# ASL2112.net
KiCad netlist of a schematic drawn in EAGLE
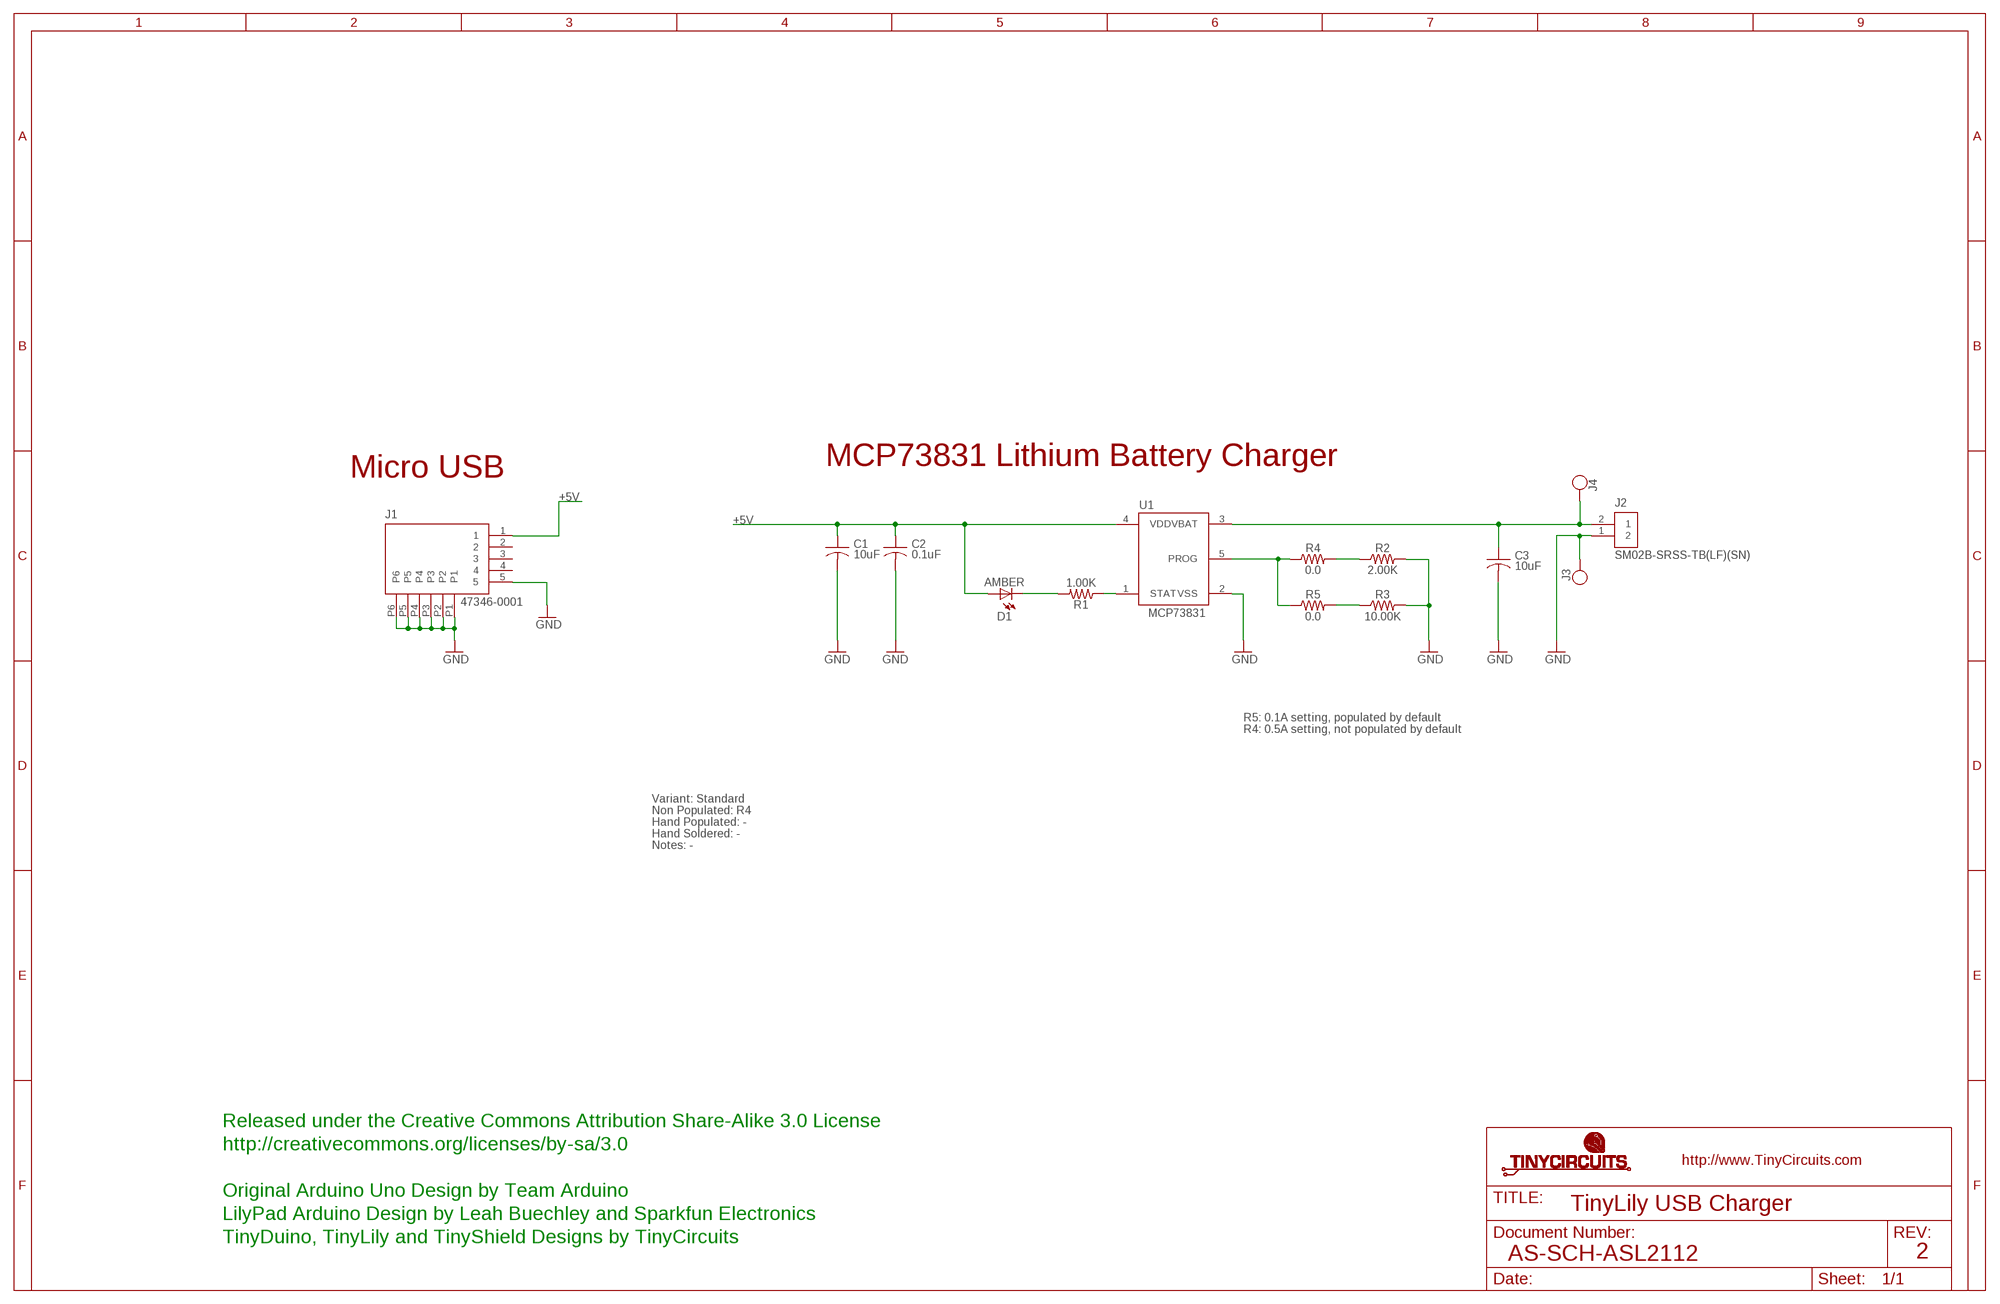
[diagram p0: schematic, sheet 1]

(export (version "E")
  (design (tool "Eeschema 10.0.6"))
  (components
    (comp (ref "C1")
      (value "10uF")
      (footprint "eagle-import:C0603")
      (fields (field (name "PARTNO") "AS-ITM-00002"))
      (libsource (lib "eagle-import") (part "AS-ITM-00002"))
    )
    (comp (ref "C2")
      (value "0.1uF")
      (footprint "eagle-import:C0402")
      (fields (field (name "PARTNO") "AS-ITM-00008"))
      (libsource (lib "eagle-import") (part "AS-ITM-00008"))
    )
    (comp (ref "C3")
      (value "10uF")
      (footprint "eagle-import:C0603")
      (fields (field (name "PARTNO") "AS-ITM-00002") (field (name "PARTNO_1") "AS-ITM-00002"))
      (libsource (lib "eagle-import") (part "AS-ITM-00002"))
    )
    (comp (ref "D1")
      (value "AMBER")
      (footprint "eagle-import:0402_LED")
      (fields (field (name "PARTNO") "AS-ITM-00058") (field (name "PARTNO_1") "AS-ITM-00058"))
      (libsource (lib "eagle-import") (part "AS-ITM-00058"))
    )
    (comp (ref "J1")
      (value "47346-0001")
      (footprint "eagle-import:MICRO_USB")
      (fields (field (name "PARTNO") "AS-ITM-00021") (field (name "PARTNO_1") "AS-ITM-00021"))
      (libsource (lib "eagle-import") (part "AS-ITM-00021"))
    )
    (comp (ref "J2")
      (value "SM02B-SRSS-TB(LF)(SN)")
      (footprint "eagle-import:JST_SH_2X1")
      (fields (field (name "PARTNO") "AS-ITM-00231"))
      (libsource (lib "eagle-import") (part "AS-ITM-00231"))
    )
    (comp (ref "J3")
      (value "PIN_1X.1\"1")
      (footprint "eagle-import:1X.1__2")
      (libsource (lib "eagle-import") (part "PIN_1X.1{dblquote}1"))
    )
    (comp (ref "J4")
      (value "PIN_1X.1\"1")
      (footprint "eagle-import:1X.1__2")
      (libsource (lib "eagle-import") (part "PIN_1X.1{dblquote}1"))
    )
    (comp (ref "R1")
      (value "1.00K")
      (footprint "eagle-import:0402")
      (fields (field (name "PARTNO") "AS-ITM-00003"))
      (libsource (lib "eagle-import") (part "AS-ITM-00003"))
    )
    (comp (ref "R2")
      (value "2.00K")
      (footprint "eagle-import:0402")
      (fields (field (name "PARTNO") "AS-ITM-00315") (field (name "PARTNO_1") "AS-ITM-00315"))
      (libsource (lib "eagle-import") (part "AS-ITM-00315"))
    )
    (comp (ref "R3")
      (value "10.00K")
      (footprint "eagle-import:0402")
      (fields (field (name "PARTNO") "AS-ITM-00032") (field (name "PARTNO_1") "AS-ITM-00032"))
      (libsource (lib "eagle-import") (part "AS-ITM-00032"))
    )
    (comp (ref "R4")
      (value "0.0")
      (footprint "eagle-import:0402")
      (fields (field (name "PARTNO") "AS-ITM-00076"))
      (libsource (lib "eagle-import") (part "AS-ITM-00076"))
    )
    (comp (ref "R5")
      (value "0.0")
      (footprint "eagle-import:0402")
      (fields (field (name "PARTNO") "AS-ITM-00076"))
      (libsource (lib "eagle-import") (part "AS-ITM-00076"))
    )
    (comp (ref "U1")
      (value "MCP73831")
      (footprint "eagle-import:SOT-23")
      (fields (field (name "PARTNO") "AS-ITM-00136"))
      (libsource (lib "eagle-import") (part "AS-ITM-00136"))
    )
  )
  (nets
    (net (code "1") (name "/+5V") (class "Default")
      (node (ref "C1") (pin "1") (pinfunction "1_1") (pintype "passive"))
      (node (ref "C2") (pin "1") (pinfunction "1_1") (pintype "passive"))
      (node (ref "D1") (pin "1") (pinfunction "A_1") (pintype "passive"))
      (node (ref "J1") (pin "1") (pinfunction "1_1") (pintype "bidirectional"))
      (node (ref "U1") (pin "4") (pinfunction "VDD_4") (pintype "bidirectional"))
    )
    (net (code "2") (name "GND") (class "Default")
      (node (ref "C1") (pin "2") (pinfunction "2_2") (pintype "passive"))
      (node (ref "C2") (pin "2") (pinfunction "2_2") (pintype "passive"))
      (node (ref "C3") (pin "2") (pinfunction "2_2") (pintype "passive"))
      (node (ref "J1") (pin "5") (pinfunction "5_5") (pintype "bidirectional"))
      (node (ref "J1") (pin "P1") (pinfunction "P1_P1") (pintype "bidirectional"))
      (node (ref "J1") (pin "P2") (pinfunction "P2_P2") (pintype "bidirectional"))
      (node (ref "J1") (pin "P3") (pinfunction "P3_P3") (pintype "bidirectional"))
      (node (ref "J1") (pin "P4") (pinfunction "P4_P4") (pintype "bidirectional"))
      (node (ref "J1") (pin "P5") (pinfunction "P5_P5") (pintype "bidirectional"))
      (node (ref "J1") (pin "P6") (pinfunction "P6_P6") (pintype "bidirectional"))
      (node (ref "J2") (pin "1") (pinfunction "2_1") (pintype "bidirectional"))
      (node (ref "J3") (pin "1") (pinfunction "1_1") (pintype "bidirectional"))
      (node (ref "R2") (pin "2") (pinfunction "2_2") (pintype "passive"))
      (node (ref "R3") (pin "2") (pinfunction "2_2") (pintype "passive"))
      (node (ref "U1") (pin "2") (pinfunction "VSS_2") (pintype "bidirectional"))
    )
    (net (code "3") (name "Net-(D1-C)") (class "Default")
      (node (ref "D1") (pin "2") (pinfunction "C_2") (pintype "passive"))
      (node (ref "R1") (pin "2") (pinfunction "2_2") (pintype "passive"))
    )
    (net (code "4") (name "Net-(J2-1)") (class "Default")
      (node (ref "C3") (pin "1") (pinfunction "1_1") (pintype "passive"))
      (node (ref "J2") (pin "2") (pinfunction "1_2") (pintype "bidirectional"))
      (node (ref "J4") (pin "1") (pinfunction "1_1") (pintype "bidirectional"))
      (node (ref "U1") (pin "3") (pinfunction "VBAT_3") (pintype "bidirectional"))
    )
    (net (code "5") (name "Net-(R2-Pad1)") (class "Default")
      (node (ref "R2") (pin "1") (pinfunction "1_1") (pintype "passive"))
      (node (ref "R4") (pin "2") (pinfunction "2_2") (pintype "passive"))
    )
    (net (code "6") (name "Net-(R3-Pad1)") (class "Default")
      (node (ref "R3") (pin "1") (pinfunction "1_1") (pintype "passive"))
      (node (ref "R5") (pin "2") (pinfunction "2_2") (pintype "passive"))
    )
    (net (code "7") (name "Net-(U1-PROG)") (class "Default")
      (node (ref "R4") (pin "1") (pinfunction "1_1") (pintype "passive"))
      (node (ref "R5") (pin "1") (pinfunction "1_1") (pintype "passive"))
      (node (ref "U1") (pin "5") (pinfunction "PROG_5") (pintype "bidirectional"))
    )
    (net (code "8") (name "Net-(U1-STAT)") (class "Default")
      (node (ref "R1") (pin "1") (pinfunction "1_1") (pintype "passive"))
      (node (ref "U1") (pin "1") (pinfunction "STAT_1") (pintype "bidirectional"))
    )
    (net (code "9") (name "unconnected-(J1-Pad2)") (class "Default")
      (node (ref "J1") (pin "2") (pinfunction "2_2") (pintype "bidirectional"))
    )
    (net (code "10") (name "unconnected-(J1-Pad3)") (class "Default")
      (node (ref "J1") (pin "3") (pinfunction "3_3") (pintype "bidirectional"))
    )
    (net (code "11") (name "unconnected-(J1-Pad4)") (class "Default")
      (node (ref "J1") (pin "4") (pinfunction "4_4") (pintype "bidirectional"))
    )
  )
)
